# Breakout1v2.net
KiCad netlist of a schematic drawn in EAGLE
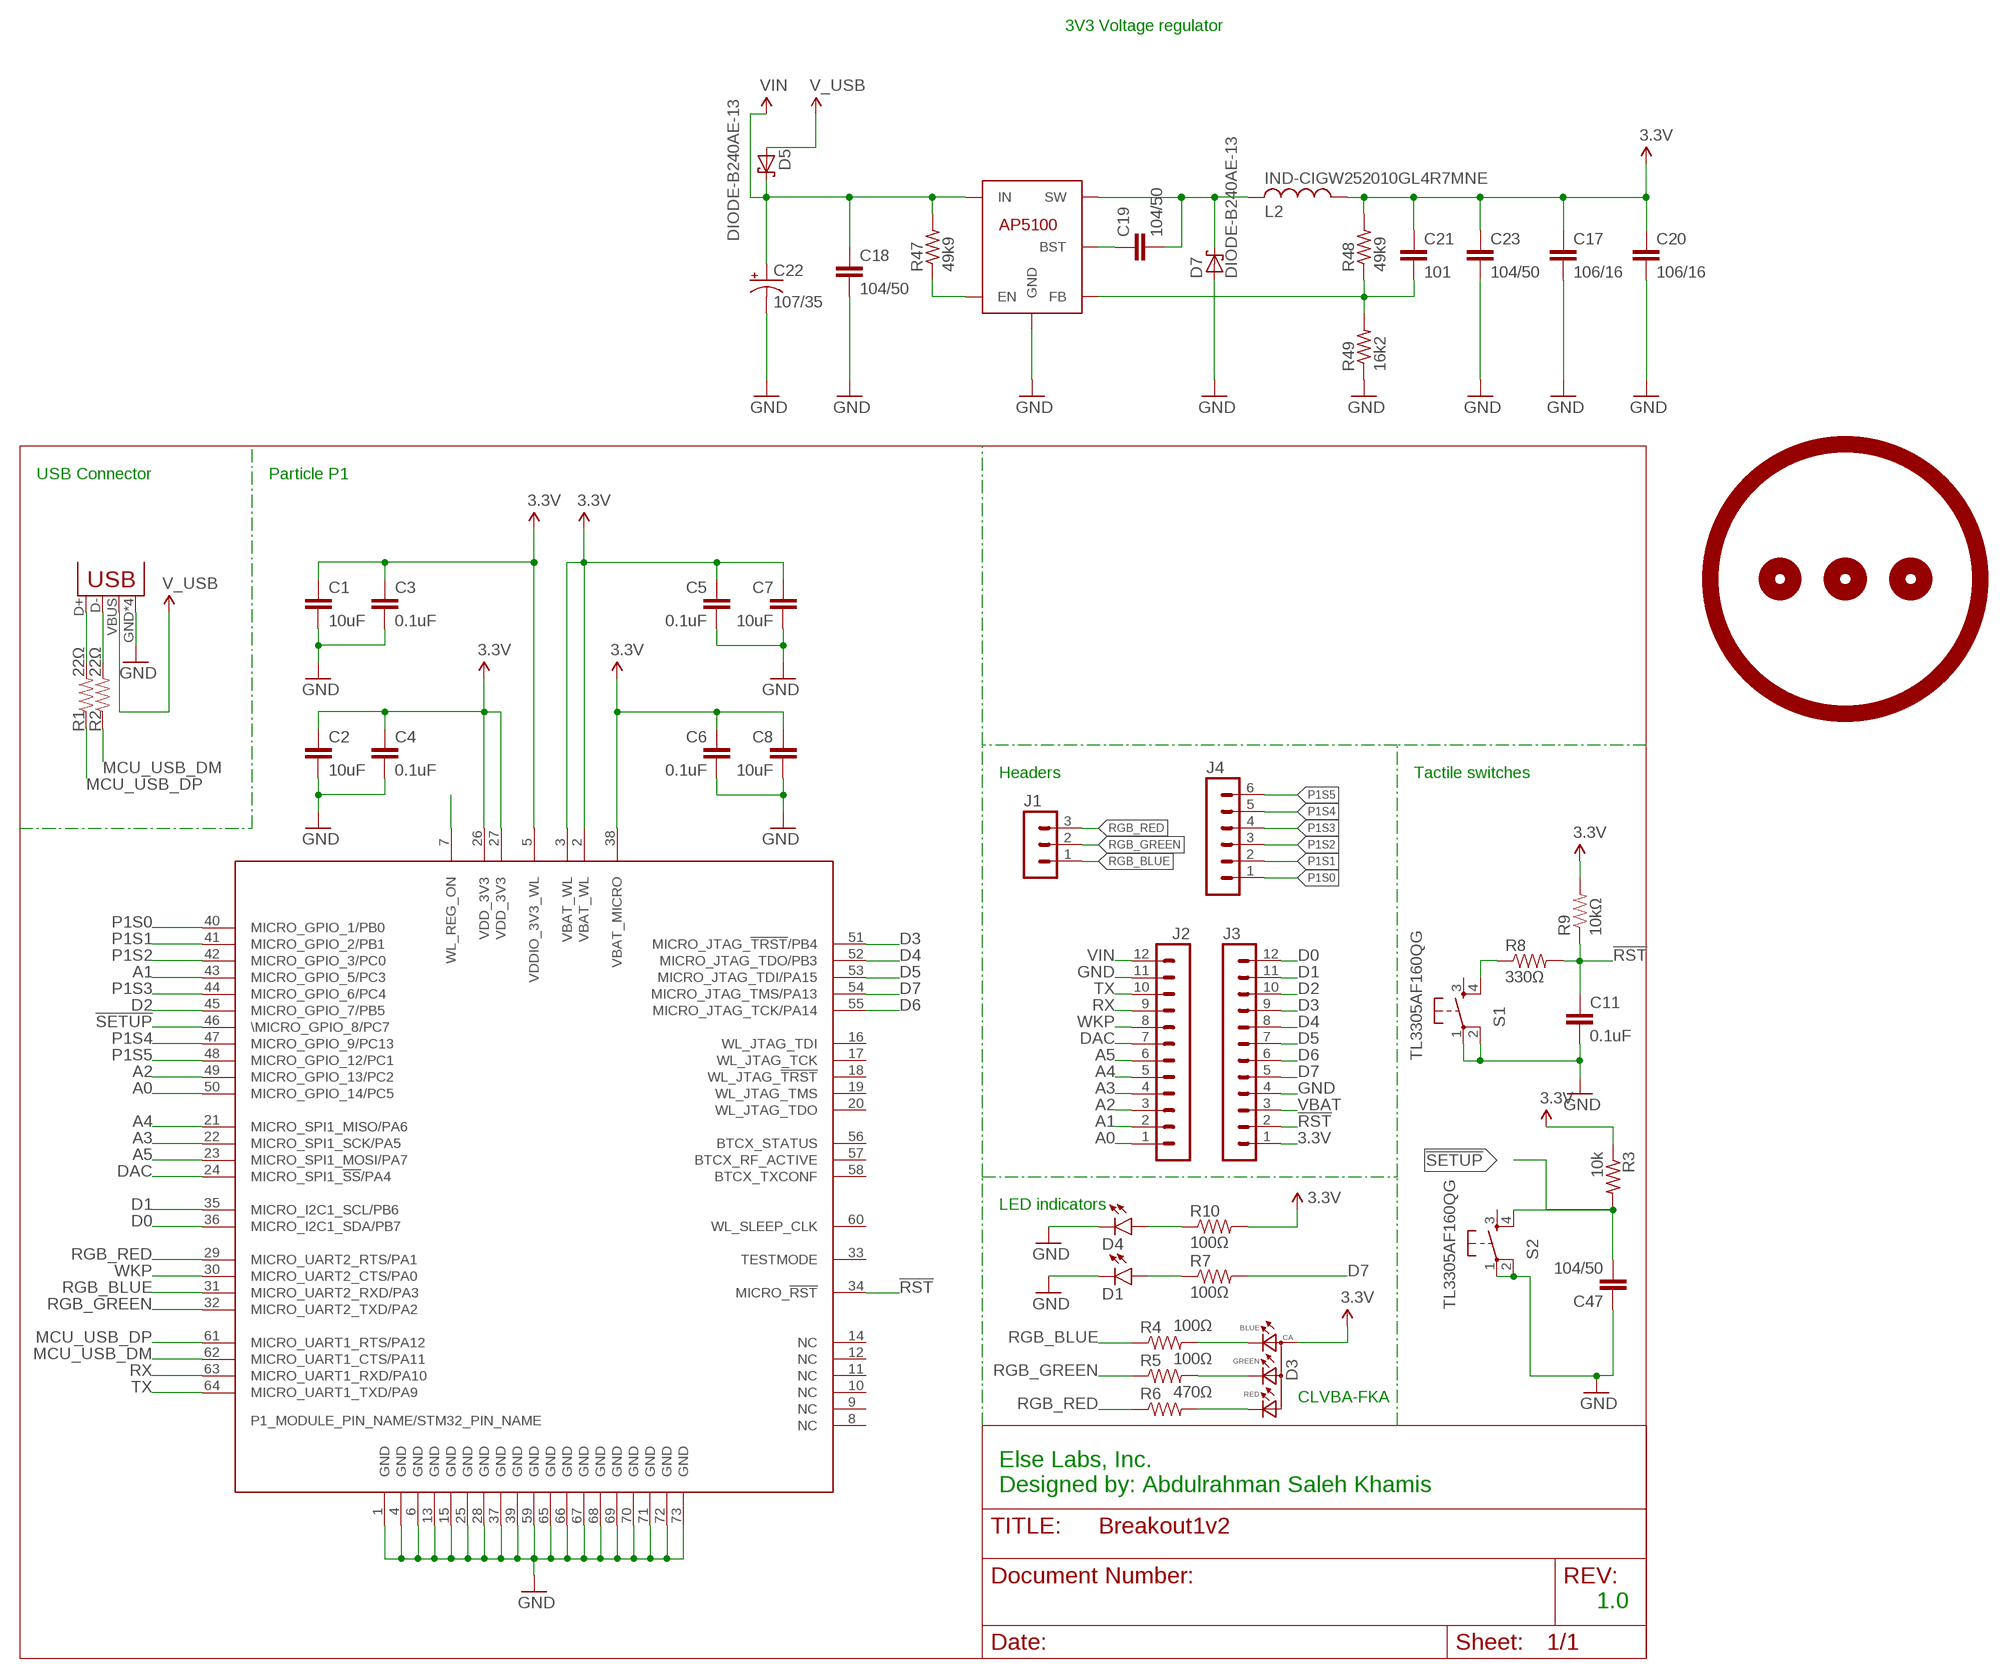
[diagram p0: schematic, sheet 1]

(export (version "E")
  (design (tool "Eeschema 10.0.6"))
  (components
    (comp (ref "C1")
      (value "10uF")
      (footprint "eagle-import:0805")
      (libsource (lib "eagle-import") (part "CAP0805"))
    )
    (comp (ref "C2")
      (value "10uF")
      (footprint "eagle-import:0805")
      (libsource (lib "eagle-import") (part "CAP0805"))
    )
    (comp (ref "C3")
      (value "0.1uF")
      (footprint "eagle-import:0805")
      (libsource (lib "eagle-import") (part "CAP0805"))
    )
    (comp (ref "C4")
      (value "0.1uF")
      (footprint "eagle-import:0805")
      (libsource (lib "eagle-import") (part "CAP0805"))
    )
    (comp (ref "C5")
      (value "0.1uF")
      (footprint "eagle-import:0805")
      (libsource (lib "eagle-import") (part "CAP0805"))
    )
    (comp (ref "C6")
      (value "0.1uF")
      (footprint "eagle-import:0805")
      (libsource (lib "eagle-import") (part "CAP0805"))
    )
    (comp (ref "C7")
      (value "10uF")
      (footprint "eagle-import:0805")
      (libsource (lib "eagle-import") (part "CAP0805"))
    )
    (comp (ref "C8")
      (value "10uF")
      (footprint "eagle-import:0805")
      (libsource (lib "eagle-import") (part "CAP0805"))
    )
    (comp (ref "C11")
      (value "0.1uF")
      (footprint "eagle-import:0805")
      (libsource (lib "eagle-import") (part "CAP0805"))
    )
    (comp (ref "C17")
      (value "106/16")
      (footprint "eagle-import:C0805")
      (libsource (lib "eagle-import") (part "C-EUC0805"))
    )
    (comp (ref "C18")
      (value "104/50")
      (footprint "eagle-import:C0603")
      (libsource (lib "eagle-import") (part "C-EUC0603"))
    )
    (comp (ref "C19")
      (value "104/50")
      (footprint "eagle-import:C0603")
      (libsource (lib "eagle-import") (part "C-EUC0603"))
    )
    (comp (ref "C20")
      (value "106/16")
      (footprint "eagle-import:C0805")
      (libsource (lib "eagle-import") (part "C-EUC0805"))
    )
    (comp (ref "C21")
      (value "101")
      (footprint "eagle-import:C0603")
      (libsource (lib "eagle-import") (part "C-EUC0603"))
    )
    (comp (ref "C22")
      (value "107/35")
      (footprint "eagle-import:UD-6,3X7,7_NICHICON")
      (libsource (lib "eagle-import") (part "CPOL-USUD-6,3X7,7"))
    )
    (comp (ref "C23")
      (value "104/50")
      (footprint "eagle-import:C0603")
      (libsource (lib "eagle-import") (part "C-EUC0603"))
    )
    (comp (ref "C47")
      (value "104/50")
      (footprint "eagle-import:C0603")
      (libsource (lib "eagle-import") (part "C-EUC0603"))
    )
    (comp (ref "D1")
      (value "LED0603")
      (footprint "eagle-import:LED-0603")
      (libsource (lib "eagle-import") (part "LED0603"))
    )
    (comp (ref "D3")
      (value "CLVBA-FKAPLCC")
      (footprint "eagle-import:4-PLCC")
      (libsource (lib "eagle-import") (part "CLVBA-FKAPLCC"))
    )
    (comp (ref "D4")
      (value "LED0603")
      (footprint "eagle-import:LED-0603")
      (libsource (lib "eagle-import") (part "LED0603"))
    )
    (comp (ref "D5")
      (value "DIODE-B240AE-13")
      (footprint "eagle-import:DO-214AC")
      (libsource (lib "eagle-import") (part "DIODE-B240AE-13"))
    )
    (comp (ref "D7")
      (value "DIODE-B240AE-13")
      (footprint "eagle-import:DO-214AC")
      (libsource (lib "eagle-import") (part "DIODE-B240AE-13"))
    )
    (comp (ref "IC5")
      (value "SMSP-BUCK-AP5100")
      (footprint "eagle-import:SOT23-6")
      (libsource (lib "eagle-import") (part "SMSP-BUCK-AP5100"))
    )
    (comp (ref "J1")
      (value "MA03-1")
      (footprint "eagle-import:MA03-1")
      (libsource (lib "eagle-import") (part "MA03-1"))
    )
    (comp (ref "J2")
      (value "MA12-1")
      (footprint "eagle-import:MA12-1")
      (libsource (lib "eagle-import") (part "MA12-1"))
    )
    (comp (ref "J3")
      (value "MA12-1")
      (footprint "eagle-import:MA12-1")
      (libsource (lib "eagle-import") (part "MA12-1"))
    )
    (comp (ref "J4")
      (value "MA06-1")
      (footprint "eagle-import:MA06-1")
      (libsource (lib "eagle-import") (part "MA06-1"))
    )
    (comp (ref "JP1")
      (value "USBUSB-MICROB-SLOT-HOLE")
      (footprint "eagle-import:USB-MICROB-SLOT-HOLE")
      (libsource (lib "eagle-import") (part "USBUSB-MICROB-SLOT-HOLE"))
    )
    (comp (ref "L2")
      (value "IND-CIGW252010GL4R7MNE")
      (footprint "eagle-import:L2520")
      (libsource (lib "eagle-import") (part "IND-CIGW252010GL4R7MNE"))
    )
    (comp (ref "R1")
      (value "22Ω")
      (footprint "eagle-import:0805")
      (libsource (lib "eagle-import") (part "RESISTOR0805-RES"))
    )
    (comp (ref "R2")
      (value "22Ω")
      (footprint "eagle-import:0805")
      (libsource (lib "eagle-import") (part "RESISTOR0805-RES"))
    )
    (comp (ref "R3")
      (value "10k")
      (footprint "eagle-import:R0603")
      (libsource (lib "eagle-import") (part "R-US_R0603"))
    )
    (comp (ref "R4")
      (value "100Ω")
      (footprint "eagle-import:0805")
      (libsource (lib "eagle-import") (part "RESISTOR0805-RES"))
    )
    (comp (ref "R5")
      (value "100Ω")
      (footprint "eagle-import:0805")
      (libsource (lib "eagle-import") (part "RESISTOR0805-RES"))
    )
    (comp (ref "R6")
      (value "470Ω")
      (footprint "eagle-import:0805")
      (libsource (lib "eagle-import") (part "RESISTOR0805-RES"))
    )
    (comp (ref "R7")
      (value "100Ω")
      (footprint "eagle-import:0805")
      (libsource (lib "eagle-import") (part "RESISTOR0805-RES"))
    )
    (comp (ref "R8")
      (value "330Ω")
      (footprint "eagle-import:0805")
      (libsource (lib "eagle-import") (part "RESISTOR0805-RES"))
    )
    (comp (ref "R9")
      (value "10kΩ")
      (footprint "eagle-import:0805")
      (libsource (lib "eagle-import") (part "RESISTOR0805-RES"))
    )
    (comp (ref "R10")
      (value "100Ω")
      (footprint "eagle-import:0805")
      (libsource (lib "eagle-import") (part "RESISTOR0805-RES"))
    )
    (comp (ref "R47")
      (value "49k9")
      (footprint "eagle-import:R0603")
      (libsource (lib "eagle-import") (part "R-US_R0603"))
    )
    (comp (ref "R48")
      (value "49k9")
      (footprint "eagle-import:R0603")
      (libsource (lib "eagle-import") (part "R-US_R0603"))
    )
    (comp (ref "R49")
      (value "16k2")
      (footprint "eagle-import:R0603")
      (libsource (lib "eagle-import") (part "R-US_R0603"))
    )
    (comp (ref "S1")
      (value "TL3305AF160QG")
      (footprint "eagle-import:TACTILE_SWITCH_SMD_4.5X4.5MM")
      (libsource (lib "eagle-import") (part "SWITCH-MOMENTARY-4.5MX4.5M"))
    )
    (comp (ref "S2")
      (value "TL3305AF160QG")
      (footprint "eagle-import:TACTILE_SWITCH_SMD_4.5X4.5MM")
      (libsource (lib "eagle-import") (part "SWITCH-MOMENTARY-4.5MX4.5M"))
    )
    (comp (ref "U$1")
      (value "LOGO")
      (footprint "eagle-import:LOGO")
      (libsource (lib "eagle-import") (part "LOGO"))
    )
    (comp (ref "UC1")
      (value "P1")
      (footprint "eagle-import:WM-N-BM-14")
      (libsource (lib "eagle-import") (part "P1"))
    )
  )
  (nets
    (net (code "1") (name "/A0") (class "Default")
      (node (ref "J2") (pin "1") (pinfunction "1_1") (pintype "passive"))
      (node (ref "UC1") (pin "50") (pinfunction "MICRO_GPIO_14/PC5_50") (pintype "bidirectional"))
    )
    (net (code "2") (name "/A1") (class "Default")
      (node (ref "J2") (pin "2") (pinfunction "2_2") (pintype "passive"))
      (node (ref "UC1") (pin "43") (pinfunction "MICRO_GPIO_5/PC3_43") (pintype "bidirectional"))
    )
    (net (code "3") (name "/A2") (class "Default")
      (node (ref "J2") (pin "3") (pinfunction "3_3") (pintype "passive"))
      (node (ref "UC1") (pin "49") (pinfunction "MICRO_GPIO_13/PC2_49") (pintype "bidirectional"))
    )
    (net (code "4") (name "/A3") (class "Default")
      (node (ref "J2") (pin "4") (pinfunction "4_4") (pintype "passive"))
      (node (ref "UC1") (pin "22") (pinfunction "MICRO_SPI1_SCK/PA5_22") (pintype "bidirectional"))
    )
    (net (code "5") (name "/A4") (class "Default")
      (node (ref "J2") (pin "5") (pinfunction "5_5") (pintype "passive"))
      (node (ref "UC1") (pin "21") (pinfunction "MICRO_SPI1_MISO/PA6_21") (pintype "bidirectional"))
    )
    (net (code "6") (name "/A5") (class "Default")
      (node (ref "J2") (pin "6") (pinfunction "6_6") (pintype "passive"))
      (node (ref "UC1") (pin "23") (pinfunction "MICRO_SPI1_MOSI/PA7_23") (pintype "bidirectional"))
    )
    (net (code "7") (name "/D0") (class "Default")
      (node (ref "J3") (pin "12") (pinfunction "12_12") (pintype "passive"))
      (node (ref "UC1") (pin "36") (pinfunction "MICRO_I2C1_SDA/PB7_36") (pintype "bidirectional"))
    )
    (net (code "8") (name "/D1") (class "Default")
      (node (ref "J3") (pin "11") (pinfunction "11_11") (pintype "passive"))
      (node (ref "UC1") (pin "35") (pinfunction "MICRO_I2C1_SCL/PB6_35") (pintype "bidirectional"))
    )
    (net (code "9") (name "/D2") (class "Default")
      (node (ref "J3") (pin "10") (pinfunction "10_10") (pintype "passive"))
      (node (ref "UC1") (pin "45") (pinfunction "MICRO_GPIO_7/PB5_45") (pintype "bidirectional"))
    )
    (net (code "10") (name "/D3") (class "Default")
      (node (ref "J3") (pin "9") (pinfunction "9_9") (pintype "passive"))
      (node (ref "UC1") (pin "51") (pinfunction "MICRO_JTAG_~{TRST}/PB4_51") (pintype "bidirectional"))
    )
    (net (code "11") (name "/D4") (class "Default")
      (node (ref "J3") (pin "8") (pinfunction "8_8") (pintype "passive"))
      (node (ref "UC1") (pin "52") (pinfunction "MICRO_JTAG_TDO/PB3_52") (pintype "bidirectional"))
    )
    (net (code "12") (name "/D5") (class "Default")
      (node (ref "J3") (pin "7") (pinfunction "7_7") (pintype "passive"))
      (node (ref "UC1") (pin "53") (pinfunction "MICRO_JTAG_TDI/PA15_53") (pintype "bidirectional"))
    )
    (net (code "13") (name "/D6") (class "Default")
      (node (ref "J3") (pin "6") (pinfunction "6_6") (pintype "passive"))
      (node (ref "UC1") (pin "55") (pinfunction "MICRO_JTAG_TCK/PA14_55") (pintype "bidirectional"))
    )
    (net (code "14") (name "/D7") (class "Default")
      (node (ref "J3") (pin "5") (pinfunction "5_5") (pintype "passive"))
      (node (ref "R7") (pin "2") (pinfunction "2_2") (pintype "passive"))
      (node (ref "UC1") (pin "54") (pinfunction "MICRO_JTAG_TMS/PA13_54") (pintype "bidirectional"))
    )
    (net (code "15") (name "/DAC") (class "Default")
      (node (ref "J2") (pin "7") (pinfunction "7_7") (pintype "passive"))
      (node (ref "UC1") (pin "24") (pinfunction "MICRO_SPI1_~{SS}/PA4_24") (pintype "bidirectional"))
    )
    (net (code "16") (name "/MCU_USB_DM") (class "Default")
      (node (ref "R2") (pin "1") (pinfunction "1_1") (pintype "passive"))
      (node (ref "UC1") (pin "62") (pinfunction "MICRO_UART1_CTS/PA11_62") (pintype "bidirectional"))
    )
    (net (code "17") (name "/MCU_USB_DP") (class "Default")
      (node (ref "R1") (pin "1") (pinfunction "1_1") (pintype "passive"))
      (node (ref "UC1") (pin "61") (pinfunction "MICRO_UART1_RTS/PA12_61") (pintype "bidirectional"))
    )
    (net (code "18") (name "/RX") (class "Default")
      (node (ref "J2") (pin "9") (pinfunction "9_9") (pintype "passive"))
      (node (ref "UC1") (pin "63") (pinfunction "MICRO_UART1_RXD/PA10_63") (pintype "bidirectional"))
    )
    (net (code "19") (name "/TX") (class "Default")
      (node (ref "J2") (pin "10") (pinfunction "10_10") (pintype "passive"))
      (node (ref "UC1") (pin "64") (pinfunction "MICRO_UART1_TXD/PA9_64") (pintype "bidirectional"))
    )
    (net (code "20") (name "/VBAT") (class "Default")
      (node (ref "J3") (pin "3") (pinfunction "3_3") (pintype "passive"))
    )
    (net (code "21") (name "/WKP") (class "Default")
      (node (ref "J2") (pin "8") (pinfunction "8_8") (pintype "passive"))
      (node (ref "UC1") (pin "30") (pinfunction "MICRO_UART2_CTS/PA0_30") (pintype "bidirectional"))
    )
    (net (code "22") (name "/~{RST}") (class "Default")
      (node (ref "C11") (pin "1") (pinfunction "1_1") (pintype "passive"))
      (node (ref "J3") (pin "2") (pinfunction "2_2") (pintype "passive"))
      (node (ref "R8") (pin "2") (pinfunction "2_2") (pintype "passive"))
      (node (ref "R9") (pin "1") (pinfunction "1_1") (pintype "passive"))
      (node (ref "UC1") (pin "34") (pinfunction "MICRO_~{RST}_34") (pintype "bidirectional"))
    )
    (net (code "23") (name "/~{SETUP}") (class "Default")
      (node (ref "C47") (pin "2") (pinfunction "2_2") (pintype "passive"))
      (node (ref "R3") (pin "2") (pinfunction "2_2") (pintype "passive"))
      (node (ref "S2") (pin "4") (pinfunction "4_4") (pintype "passive"))
      (node (ref "UC1") (pin "46") (pinfunction "\\MICRO_GPIO_8/PC7_46") (pintype "bidirectional"))
    )
    (net (code "24") (name "3.3V") (class "Default")
      (node (ref "C1") (pin "1") (pinfunction "1_1") (pintype "passive"))
      (node (ref "C17") (pin "1") (pinfunction "1_1") (pintype "passive"))
      (node (ref "C2") (pin "1") (pinfunction "1_1") (pintype "passive"))
      (node (ref "C20") (pin "1") (pinfunction "1_1") (pintype "passive"))
      (node (ref "C21") (pin "1") (pinfunction "1_1") (pintype "passive"))
      (node (ref "C23") (pin "1") (pinfunction "1_1") (pintype "passive"))
      (node (ref "C3") (pin "1") (pinfunction "1_1") (pintype "passive"))
      (node (ref "C4") (pin "1") (pinfunction "1_1") (pintype "passive"))
      (node (ref "C5") (pin "1") (pinfunction "1_1") (pintype "passive"))
      (node (ref "C6") (pin "1") (pinfunction "1_1") (pintype "passive"))
      (node (ref "C7") (pin "1") (pinfunction "1_1") (pintype "passive"))
      (node (ref "C8") (pin "1") (pinfunction "1_1") (pintype "passive"))
      (node (ref "D3") (pin "2") (pinfunction "ANODE_2") (pintype "passive"))
      (node (ref "J3") (pin "1") (pinfunction "1_1") (pintype "passive"))
      (node (ref "L2") (pin "P$1") (pinfunction "1_P$1") (pintype "passive"))
      (node (ref "R10") (pin "2") (pinfunction "2_2") (pintype "passive"))
      (node (ref "R3") (pin "1") (pinfunction "1_1") (pintype "passive"))
      (node (ref "R48") (pin "2") (pinfunction "2_2") (pintype "passive"))
      (node (ref "R9") (pin "2") (pinfunction "2_2") (pintype "passive"))
      (node (ref "UC1") (pin "2") (pinfunction "VBAT_WL_2") (pintype "bidirectional"))
      (node (ref "UC1") (pin "26") (pinfunction "VDD_3V3_26") (pintype "bidirectional"))
      (node (ref "UC1") (pin "27") (pinfunction "VDD_3V3_27") (pintype "bidirectional"))
      (node (ref "UC1") (pin "3") (pinfunction "VBAT_WL_3") (pintype "bidirectional"))
      (node (ref "UC1") (pin "38") (pinfunction "VBAT_MICRO_38") (pintype "bidirectional"))
      (node (ref "UC1") (pin "5") (pinfunction "VDDIO_3V3_WL_5") (pintype "bidirectional"))
    )
    (net (code "25") (name "GND") (class "Default")
      (node (ref "C1") (pin "2") (pinfunction "2_2") (pintype "passive"))
      (node (ref "C11") (pin "2") (pinfunction "2_2") (pintype "passive"))
      (node (ref "C17") (pin "2") (pinfunction "2_2") (pintype "passive"))
      (node (ref "C18") (pin "2") (pinfunction "2_2") (pintype "passive"))
      (node (ref "C2") (pin "2") (pinfunction "2_2") (pintype "passive"))
      (node (ref "C20") (pin "2") (pinfunction "2_2") (pintype "passive"))
      (node (ref "C22") (pin "-") (pinfunction "-_-") (pintype "passive"))
      (node (ref "C23") (pin "2") (pinfunction "2_2") (pintype "passive"))
      (node (ref "C3") (pin "2") (pinfunction "2_2") (pintype "passive"))
      (node (ref "C4") (pin "2") (pinfunction "2_2") (pintype "passive"))
      (node (ref "C47") (pin "1") (pinfunction "1_1") (pintype "passive"))
      (node (ref "C5") (pin "2") (pinfunction "2_2") (pintype "passive"))
      (node (ref "C6") (pin "2") (pinfunction "2_2") (pintype "passive"))
      (node (ref "C7") (pin "2") (pinfunction "2_2") (pintype "passive"))
      (node (ref "C8") (pin "2") (pinfunction "2_2") (pintype "passive"))
      (node (ref "D1") (pin "C") (pinfunction "C_C") (pintype "passive"))
      (node (ref "D4") (pin "C") (pinfunction "C_C") (pintype "passive"))
      (node (ref "D7") (pin "A") (pinfunction "A_A") (pintype "passive"))
      (node (ref "IC5") (pin "2") (pinfunction "GND_2") (pintype "bidirectional"))
      (node (ref "J2") (pin "11") (pinfunction "11_11") (pintype "passive"))
      (node (ref "J3") (pin "4") (pinfunction "4_4") (pintype "passive"))
      (node (ref "JP1") (pin "GND") (pinfunction "GND_GND") (pintype "bidirectional"))
      (node (ref "JP1") (pin "P$1") (pinfunction "GND_P$1") (pintype "bidirectional"))
      (node (ref "JP1") (pin "P$2") (pinfunction "GND_P$2") (pintype "bidirectional"))
      (node (ref "JP1") (pin "P$3") (pinfunction "GND_P$3") (pintype "bidirectional"))
      (node (ref "R49") (pin "1") (pinfunction "1_1") (pintype "passive"))
      (node (ref "S1") (pin "1") (pinfunction "1_1") (pintype "passive"))
      (node (ref "S1") (pin "2") (pinfunction "2_2") (pintype "passive"))
      (node (ref "S2") (pin "1") (pinfunction "1_1") (pintype "passive"))
      (node (ref "S2") (pin "2") (pinfunction "2_2") (pintype "passive"))
      (node (ref "UC1") (pin "1") (pinfunction "GND_1") (pintype "bidirectional"))
      (node (ref "UC1") (pin "13") (pinfunction "GND_13") (pintype "bidirectional"))
      (node (ref "UC1") (pin "15") (pinfunction "GND_15") (pintype "bidirectional"))
      (node (ref "UC1") (pin "25") (pinfunction "GND_25") (pintype "bidirectional"))
      (node (ref "UC1") (pin "28") (pinfunction "GND_28") (pintype "bidirectional"))
      (node (ref "UC1") (pin "37") (pinfunction "GND_37") (pintype "bidirectional"))
      (node (ref "UC1") (pin "39") (pinfunction "GND_39") (pintype "bidirectional"))
      (node (ref "UC1") (pin "4") (pinfunction "GND_4") (pintype "bidirectional"))
      (node (ref "UC1") (pin "59") (pinfunction "GND_59") (pintype "bidirectional"))
      (node (ref "UC1") (pin "6") (pinfunction "GND_6") (pintype "bidirectional"))
      (node (ref "UC1") (pin "65") (pinfunction "GND_65") (pintype "bidirectional"))
      (node (ref "UC1") (pin "66") (pinfunction "GND_66") (pintype "bidirectional"))
      (node (ref "UC1") (pin "67") (pinfunction "GND_67") (pintype "bidirectional"))
      (node (ref "UC1") (pin "68") (pinfunction "GND_68") (pintype "bidirectional"))
      (node (ref "UC1") (pin "69") (pinfunction "GND_69") (pintype "bidirectional"))
      (node (ref "UC1") (pin "70") (pinfunction "GND_70") (pintype "bidirectional"))
      (node (ref "UC1") (pin "71") (pinfunction "GND_71") (pintype "bidirectional"))
      (node (ref "UC1") (pin "72") (pinfunction "GND_72") (pintype "bidirectional"))
      (node (ref "UC1") (pin "73") (pinfunction "GND_73") (pintype "bidirectional"))
    )
    (net (code "26") (name "Net-(D1-PadA)") (class "Default")
      (node (ref "D1") (pin "A") (pinfunction "A_A") (pintype "passive"))
      (node (ref "R7") (pin "1") (pinfunction "1_1") (pintype "passive"))
    )
    (net (code "27") (name "Net-(D3-BLUE)") (class "Default")
      (node (ref "D3") (pin "3") (pinfunction "BLUE_3") (pintype "passive"))
      (node (ref "R4") (pin "2") (pinfunction "2_2") (pintype "passive"))
    )
    (net (code "28") (name "Net-(D3-GREEN)") (class "Default")
      (node (ref "D3") (pin "4") (pinfunction "GREEN_4") (pintype "passive"))
      (node (ref "R5") (pin "2") (pinfunction "2_2") (pintype "passive"))
    )
    (net (code "29") (name "Net-(D3-RED)") (class "Default")
      (node (ref "D3") (pin "1") (pinfunction "RED_1") (pintype "passive"))
      (node (ref "R6") (pin "2") (pinfunction "2_2") (pintype "passive"))
    )
    (net (code "30") (name "Net-(D4-PadA)") (class "Default")
      (node (ref "D4") (pin "A") (pinfunction "A_A") (pintype "passive"))
      (node (ref "R10") (pin "1") (pinfunction "1_1") (pintype "passive"))
    )
    (net (code "31") (name "Net-(IC5-BST)") (class "Default")
      (node (ref "C19") (pin "1") (pinfunction "1_1") (pintype "passive"))
      (node (ref "IC5") (pin "1") (pinfunction "BST_1") (pintype "bidirectional"))
    )
    (net (code "32") (name "Net-(IC5-EN)") (class "Default")
      (node (ref "IC5") (pin "4") (pinfunction "EN_4") (pintype "bidirectional"))
      (node (ref "R47") (pin "1") (pinfunction "1_1") (pintype "passive"))
    )
    (net (code "33") (name "Net-(IC5-FB)") (class "Default")
      (node (ref "C21") (pin "2") (pinfunction "2_2") (pintype "passive"))
      (node (ref "IC5") (pin "3") (pinfunction "FB_3") (pintype "bidirectional"))
      (node (ref "R48") (pin "1") (pinfunction "1_1") (pintype "passive"))
      (node (ref "R49") (pin "2") (pinfunction "2_2") (pintype "passive"))
    )
    (net (code "34") (name "Net-(IC5-SW)") (class "Default")
      (node (ref "C19") (pin "2") (pinfunction "2_2") (pintype "passive"))
      (node (ref "D7") (pin "C") (pinfunction "C_C") (pintype "passive"))
      (node (ref "IC5") (pin "6") (pinfunction "SW_6") (pintype "bidirectional"))
      (node (ref "L2") (pin "P$2") (pinfunction "2_P$2") (pintype "passive"))
    )
    (net (code "35") (name "Net-(JP1-PadD+)") (class "Default")
      (node (ref "JP1") (pin "D+") (pinfunction "D+_D+") (pintype "bidirectional"))
      (node (ref "R1") (pin "2") (pinfunction "2_2") (pintype "passive"))
    )
    (net (code "36") (name "Net-(JP1-PadD-)") (class "Default")
      (node (ref "JP1") (pin "D-") (pinfunction "D-_D-") (pintype "bidirectional"))
      (node (ref "R2") (pin "2") (pinfunction "2_2") (pintype "passive"))
    )
    (net (code "37") (name "Net-(R8-Pad1)") (class "Default")
      (node (ref "R8") (pin "1") (pinfunction "1_1") (pintype "passive"))
      (node (ref "S1") (pin "4") (pinfunction "4_4") (pintype "passive"))
    )
    (net (code "38") (name "P1S0") (class "Default")
      (node (ref "J4") (pin "1") (pinfunction "1_1") (pintype "passive"))
      (node (ref "UC1") (pin "40") (pinfunction "MICRO_GPIO_1/PB0_40") (pintype "bidirectional"))
    )
    (net (code "39") (name "P1S1") (class "Default")
      (node (ref "J4") (pin "2") (pinfunction "2_2") (pintype "passive"))
      (node (ref "UC1") (pin "41") (pinfunction "MICRO_GPIO_2/PB1_41") (pintype "bidirectional"))
    )
    (net (code "40") (name "P1S2") (class "Default")
      (node (ref "J4") (pin "3") (pinfunction "3_3") (pintype "passive"))
      (node (ref "UC1") (pin "42") (pinfunction "MICRO_GPIO_3/PC0_42") (pintype "bidirectional"))
    )
    (net (code "41") (name "P1S3") (class "Default")
      (node (ref "J4") (pin "4") (pinfunction "4_4") (pintype "passive"))
      (node (ref "UC1") (pin "44") (pinfunction "MICRO_GPIO_6/PC4_44") (pintype "bidirectional"))
    )
    (net (code "42") (name "P1S4") (class "Default")
      (node (ref "J4") (pin "5") (pinfunction "5_5") (pintype "passive"))
      (node (ref "UC1") (pin "47") (pinfunction "MICRO_GPIO_9/PC13_47") (pintype "bidirectional"))
    )
    (net (code "43") (name "P1S5") (class "Default")
      (node (ref "J4") (pin "6") (pinfunction "6_6") (pintype "passive"))
      (node (ref "UC1") (pin "48") (pinfunction "MICRO_GPIO_12/PC1_48") (pintype "bidirectional"))
    )
    (net (code "44") (name "RGB_BLUE") (class "Default")
      (node (ref "J1") (pin "1") (pinfunction "1_1") (pintype "passive"))
      (node (ref "R4") (pin "1") (pinfunction "1_1") (pintype "passive"))
      (node (ref "UC1") (pin "31") (pinfunction "MICRO_UART2_RXD/PA3_31") (pintype "bidirectional"))
    )
    (net (code "45") (name "RGB_GREEN") (class "Default")
      (node (ref "J1") (pin "2") (pinfunction "2_2") (pintype "passive"))
      (node (ref "R5") (pin "1") (pinfunction "1_1") (pintype "passive"))
      (node (ref "UC1") (pin "32") (pinfunction "MICRO_UART2_TXD/PA2_32") (pintype "bidirectional"))
    )
    (net (code "46") (name "RGB_RED") (class "Default")
      (node (ref "J1") (pin "3") (pinfunction "3_3") (pintype "passive"))
      (node (ref "R6") (pin "1") (pinfunction "1_1") (pintype "passive"))
      (node (ref "UC1") (pin "29") (pinfunction "MICRO_UART2_RTS/PA1_29") (pintype "bidirectional"))
    )
    (net (code "47") (name "VIN") (class "Default")
      (node (ref "C18") (pin "1") (pinfunction "1_1") (pintype "passive"))
      (node (ref "C22") (pin "+") (pinfunction "+_+") (pintype "passive"))
      (node (ref "D5") (pin "C") (pinfunction "C_C") (pintype "passive"))
      (node (ref "IC5") (pin "5") (pinfunction "IN_5") (pintype "bidirectional"))
      (node (ref "J2") (pin "12") (pinfunction "12_12") (pintype "passive"))
      (node (ref "R47") (pin "2") (pinfunction "2_2") (pintype "passive"))
    )
    (net (code "48") (name "V_USB") (class "Default")
      (node (ref "D5") (pin "A") (pinfunction "A_A") (pintype "passive"))
      (node (ref "JP1") (pin "VBUS") (pinfunction "VBUS_VBUS") (pintype "bidirectional"))
    )
    (net (code "49") (name "unconnected-(S1-Pad3)") (class "Default")
      (node (ref "S1") (pin "3") (pinfunction "3_3") (pintype "passive"))
    )
    (net (code "50") (name "unconnected-(S2-Pad3)") (class "Default")
      (node (ref "S2") (pin "3") (pinfunction "3_3") (pintype "passive"))
    )
    (net (code "51") (name "unconnected-(UC1-BTCX_RF_ACTIVE-Pad57)") (class "Default")
      (node (ref "UC1") (pin "57") (pinfunction "BTCX_RF_ACTIVE_57") (pintype "bidirectional"))
    )
    (net (code "52") (name "unconnected-(UC1-BTCX_STATUS-Pad56)") (class "Default")
      (node (ref "UC1") (pin "56") (pinfunction "BTCX_STATUS_56") (pintype "bidirectional"))
    )
    (net (code "53") (name "unconnected-(UC1-BTCX_TXCONF-Pad58)") (class "Default")
      (node (ref "UC1") (pin "58") (pinfunction "BTCX_TXCONF_58") (pintype "bidirectional"))
    )
    (net (code "54") (name "unconnected-(UC1-NC-Pad8)") (class "Default")
      (node (ref "UC1") (pin "8") (pinfunction "NC_8") (pintype "bidirectional"))
    )
    (net (code "55") (name "unconnected-(UC1-NC-Pad9)") (class "Default")
      (node (ref "UC1") (pin "9") (pinfunction "NC_9") (pintype "bidirectional"))
    )
    (net (code "56") (name "unconnected-(UC1-NC-Pad10)") (class "Default")
      (node (ref "UC1") (pin "10") (pinfunction "NC_10") (pintype "bidirectional"))
    )
    (net (code "57") (name "unconnected-(UC1-NC-Pad11)") (class "Default")
      (node (ref "UC1") (pin "11") (pinfunction "NC_11") (pintype "bidirectional"))
    )
    (net (code "58") (name "unconnected-(UC1-NC-Pad12)") (class "Default")
      (node (ref "UC1") (pin "12") (pinfunction "NC_12") (pintype "bidirectional"))
    )
    (net (code "59") (name "unconnected-(UC1-NC-Pad14)") (class "Default")
      (node (ref "UC1") (pin "14") (pinfunction "NC_14") (pintype "bidirectional"))
    )
    (net (code "60") (name "unconnected-(UC1-TESTMODE-Pad33)") (class "Default")
      (node (ref "UC1") (pin "33") (pinfunction "TESTMODE_33") (pintype "bidirectional"))
    )
    (net (code "61") (name "unconnected-(UC1-WL_JTAG_TCK-Pad17)") (class "Default")
      (node (ref "UC1") (pin "17") (pinfunction "WL_JTAG_TCK_17") (pintype "bidirectional"))
    )
    (net (code "62") (name "unconnected-(UC1-WL_JTAG_TDI-Pad16)") (class "Default")
      (node (ref "UC1") (pin "16") (pinfunction "WL_JTAG_TDI_16") (pintype "bidirectional"))
    )
    (net (code "63") (name "unconnected-(UC1-WL_JTAG_TDO-Pad20)") (class "Default")
      (node (ref "UC1") (pin "20") (pinfunction "WL_JTAG_TDO_20") (pintype "bidirectional"))
    )
    (net (code "64") (name "unconnected-(UC1-WL_JTAG_TMS-Pad19)") (class "Default")
      (node (ref "UC1") (pin "19") (pinfunction "WL_JTAG_TMS_19") (pintype "bidirectional"))
    )
    (net (code "65") (name "unconnected-(UC1-WL_JTAG_~{TRST}-Pad18)") (class "Default")
      (node (ref "UC1") (pin "18") (pinfunction "WL_JTAG_~{TRST}_18") (pintype "bidirectional"))
    )
    (net (code "66") (name "unconnected-(UC1-WL_REG_ON-Pad7)") (class "Default")
      (node (ref "UC1") (pin "7") (pinfunction "WL_REG_ON_7") (pintype "bidirectional"))
    )
    (net (code "67") (name "unconnected-(UC1-WL_SLEEP_CLK-Pad60)") (class "Default")
      (node (ref "UC1") (pin "60") (pinfunction "WL_SLEEP_CLK_60") (pintype "bidirectional"))
    )
  )
)
